# LEDDisplays-v00.net
KiCad netlist of a schematic drawn in EAGLE
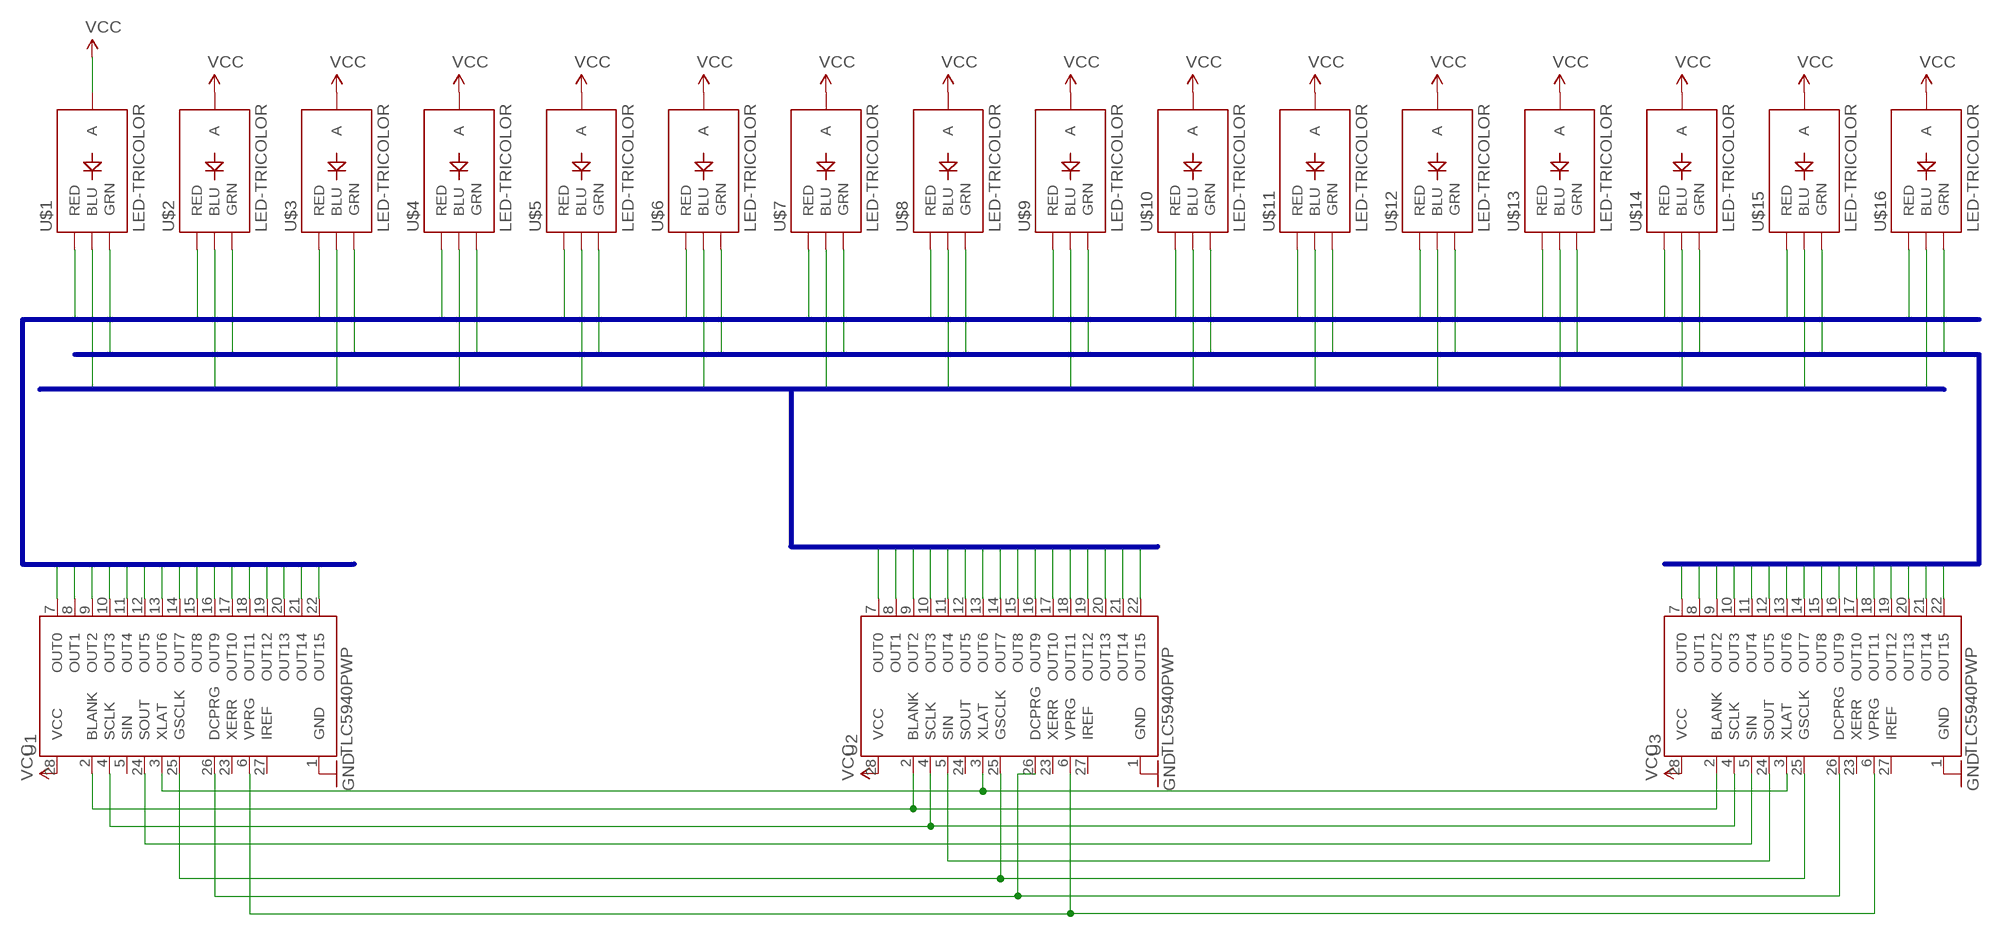
[diagram p0: schematic, sheet 1]

(export (version "E")
  (design (tool "Eeschema 10.0.6"))
  (components
    (comp (ref "U$1")
      (value "LED-TRICOLOR")
      (footprint "eagle-import:LED-TRICOLOR-SMD")
      (libsource (lib "eagle-import") (part "LED-TRICOLOR"))
    )
    (comp (ref "U$2")
      (value "LED-TRICOLOR")
      (footprint "eagle-import:LED-TRICOLOR-SMD")
      (libsource (lib "eagle-import") (part "LED-TRICOLOR"))
    )
    (comp (ref "U$3")
      (value "LED-TRICOLOR")
      (footprint "eagle-import:LED-TRICOLOR-SMD")
      (libsource (lib "eagle-import") (part "LED-TRICOLOR"))
    )
    (comp (ref "U$4")
      (value "LED-TRICOLOR")
      (footprint "eagle-import:LED-TRICOLOR-SMD")
      (libsource (lib "eagle-import") (part "LED-TRICOLOR"))
    )
    (comp (ref "U$5")
      (value "LED-TRICOLOR")
      (footprint "eagle-import:LED-TRICOLOR-SMD")
      (libsource (lib "eagle-import") (part "LED-TRICOLOR"))
    )
    (comp (ref "U$6")
      (value "LED-TRICOLOR")
      (footprint "eagle-import:LED-TRICOLOR-SMD")
      (libsource (lib "eagle-import") (part "LED-TRICOLOR"))
    )
    (comp (ref "U$7")
      (value "LED-TRICOLOR")
      (footprint "eagle-import:LED-TRICOLOR-SMD")
      (libsource (lib "eagle-import") (part "LED-TRICOLOR"))
    )
    (comp (ref "U$8")
      (value "LED-TRICOLOR")
      (footprint "eagle-import:LED-TRICOLOR-SMD")
      (libsource (lib "eagle-import") (part "LED-TRICOLOR"))
    )
    (comp (ref "U$9")
      (value "LED-TRICOLOR")
      (footprint "eagle-import:LED-TRICOLOR-SMD")
      (libsource (lib "eagle-import") (part "LED-TRICOLOR"))
    )
    (comp (ref "U$10")
      (value "LED-TRICOLOR")
      (footprint "eagle-import:LED-TRICOLOR-SMD")
      (libsource (lib "eagle-import") (part "LED-TRICOLOR"))
    )
    (comp (ref "U$11")
      (value "LED-TRICOLOR")
      (footprint "eagle-import:LED-TRICOLOR-SMD")
      (libsource (lib "eagle-import") (part "LED-TRICOLOR"))
    )
    (comp (ref "U$12")
      (value "LED-TRICOLOR")
      (footprint "eagle-import:LED-TRICOLOR-SMD")
      (libsource (lib "eagle-import") (part "LED-TRICOLOR"))
    )
    (comp (ref "U$13")
      (value "LED-TRICOLOR")
      (footprint "eagle-import:LED-TRICOLOR-SMD")
      (libsource (lib "eagle-import") (part "LED-TRICOLOR"))
    )
    (comp (ref "U$14")
      (value "LED-TRICOLOR")
      (footprint "eagle-import:LED-TRICOLOR-SMD")
      (libsource (lib "eagle-import") (part "LED-TRICOLOR"))
    )
    (comp (ref "U$15")
      (value "LED-TRICOLOR")
      (footprint "eagle-import:LED-TRICOLOR-SMD")
      (libsource (lib "eagle-import") (part "LED-TRICOLOR"))
    )
    (comp (ref "U$16")
      (value "LED-TRICOLOR")
      (footprint "eagle-import:LED-TRICOLOR-SMD")
      (libsource (lib "eagle-import") (part "LED-TRICOLOR"))
    )
    (comp (ref "U1")
      (value "TLC5940PWP")
      (footprint "eagle-import:TSSOP28-GROUNDPAD")
      (libsource (lib "eagle-import") (part "TLC5940PWP"))
    )
    (comp (ref "U2")
      (value "TLC5940PWP")
      (footprint "eagle-import:TSSOP28-GROUNDPAD")
      (libsource (lib "eagle-import") (part "TLC5940PWP"))
    )
    (comp (ref "U3")
      (value "TLC5940PWP")
      (footprint "eagle-import:TSSOP28-GROUNDPAD")
      (libsource (lib "eagle-import") (part "TLC5940PWP"))
    )
  )
  (nets
    (net (code "1") (name "/B1") (class "Default")
      (node (ref "U$1") (pin "B") (pinfunction "BLU_B") (pintype "bidirectional"))
      (node (ref "U2") (pin "7") (pinfunction "OUT0_7") (pintype "bidirectional"))
    )
    (net (code "2") (name "/B2") (class "Default")
      (node (ref "U$2") (pin "B") (pinfunction "BLU_B") (pintype "bidirectional"))
      (node (ref "U2") (pin "8") (pinfunction "OUT1_8") (pintype "bidirectional"))
    )
    (net (code "3") (name "/B3") (class "Default")
      (node (ref "U$3") (pin "B") (pinfunction "BLU_B") (pintype "bidirectional"))
      (node (ref "U2") (pin "9") (pinfunction "OUT2_9") (pintype "bidirectional"))
    )
    (net (code "4") (name "/B4") (class "Default")
      (node (ref "U$4") (pin "B") (pinfunction "BLU_B") (pintype "bidirectional"))
      (node (ref "U2") (pin "10") (pinfunction "OUT3_10") (pintype "bidirectional"))
    )
    (net (code "5") (name "/B5") (class "Default")
      (node (ref "U$5") (pin "B") (pinfunction "BLU_B") (pintype "bidirectional"))
      (node (ref "U2") (pin "11") (pinfunction "OUT4_11") (pintype "bidirectional"))
    )
    (net (code "6") (name "/B6") (class "Default")
      (node (ref "U$6") (pin "B") (pinfunction "BLU_B") (pintype "bidirectional"))
      (node (ref "U2") (pin "12") (pinfunction "OUT5_12") (pintype "bidirectional"))
    )
    (net (code "7") (name "/B7") (class "Default")
      (node (ref "U$7") (pin "B") (pinfunction "BLU_B") (pintype "bidirectional"))
      (node (ref "U2") (pin "13") (pinfunction "OUT6_13") (pintype "bidirectional"))
    )
    (net (code "8") (name "/B8") (class "Default")
      (node (ref "U$8") (pin "B") (pinfunction "BLU_B") (pintype "bidirectional"))
      (node (ref "U2") (pin "14") (pinfunction "OUT7_14") (pintype "bidirectional"))
    )
    (net (code "9") (name "/B9") (class "Default")
      (node (ref "U$9") (pin "B") (pinfunction "BLU_B") (pintype "bidirectional"))
      (node (ref "U2") (pin "15") (pinfunction "OUT8_15") (pintype "bidirectional"))
    )
    (net (code "10") (name "/B10") (class "Default")
      (node (ref "U$10") (pin "B") (pinfunction "BLU_B") (pintype "bidirectional"))
      (node (ref "U2") (pin "16") (pinfunction "OUT9_16") (pintype "bidirectional"))
    )
    (net (code "11") (name "/B11") (class "Default")
      (node (ref "U$11") (pin "B") (pinfunction "BLU_B") (pintype "bidirectional"))
      (node (ref "U2") (pin "17") (pinfunction "OUT10_17") (pintype "bidirectional"))
    )
    (net (code "12") (name "/B12") (class "Default")
      (node (ref "U$12") (pin "B") (pinfunction "BLU_B") (pintype "bidirectional"))
      (node (ref "U2") (pin "18") (pinfunction "OUT11_18") (pintype "bidirectional"))
    )
    (net (code "13") (name "/B13") (class "Default")
      (node (ref "U$13") (pin "B") (pinfunction "BLU_B") (pintype "bidirectional"))
      (node (ref "U2") (pin "19") (pinfunction "OUT12_19") (pintype "bidirectional"))
    )
    (net (code "14") (name "/B14") (class "Default")
      (node (ref "U$14") (pin "B") (pinfunction "BLU_B") (pintype "bidirectional"))
      (node (ref "U2") (pin "20") (pinfunction "OUT13_20") (pintype "bidirectional"))
    )
    (net (code "15") (name "/B15") (class "Default")
      (node (ref "U$15") (pin "B") (pinfunction "BLU_B") (pintype "bidirectional"))
      (node (ref "U2") (pin "21") (pinfunction "OUT14_21") (pintype "bidirectional"))
    )
    (net (code "16") (name "/B16") (class "Default")
      (node (ref "U$16") (pin "B") (pinfunction "BLU_B") (pintype "bidirectional"))
      (node (ref "U2") (pin "22") (pinfunction "OUT15_22") (pintype "bidirectional"))
    )
    (net (code "17") (name "/G1") (class "Default")
      (node (ref "U$1") (pin "G") (pinfunction "GRN_G") (pintype "bidirectional"))
      (node (ref "U3") (pin "7") (pinfunction "OUT0_7") (pintype "bidirectional"))
    )
    (net (code "18") (name "/G2") (class "Default")
      (node (ref "U$2") (pin "G") (pinfunction "GRN_G") (pintype "bidirectional"))
      (node (ref "U3") (pin "8") (pinfunction "OUT1_8") (pintype "bidirectional"))
    )
    (net (code "19") (name "/G3") (class "Default")
      (node (ref "U$3") (pin "G") (pinfunction "GRN_G") (pintype "bidirectional"))
      (node (ref "U3") (pin "9") (pinfunction "OUT2_9") (pintype "bidirectional"))
    )
    (net (code "20") (name "/G4") (class "Default")
      (node (ref "U$4") (pin "G") (pinfunction "GRN_G") (pintype "bidirectional"))
      (node (ref "U3") (pin "10") (pinfunction "OUT3_10") (pintype "bidirectional"))
    )
    (net (code "21") (name "/G5") (class "Default")
      (node (ref "U$5") (pin "G") (pinfunction "GRN_G") (pintype "bidirectional"))
      (node (ref "U3") (pin "11") (pinfunction "OUT4_11") (pintype "bidirectional"))
    )
    (net (code "22") (name "/G6") (class "Default")
      (node (ref "U$6") (pin "G") (pinfunction "GRN_G") (pintype "bidirectional"))
      (node (ref "U3") (pin "12") (pinfunction "OUT5_12") (pintype "bidirectional"))
    )
    (net (code "23") (name "/G7") (class "Default")
      (node (ref "U$7") (pin "G") (pinfunction "GRN_G") (pintype "bidirectional"))
      (node (ref "U3") (pin "13") (pinfunction "OUT6_13") (pintype "bidirectional"))
    )
    (net (code "24") (name "/G8") (class "Default")
      (node (ref "U$8") (pin "G") (pinfunction "GRN_G") (pintype "bidirectional"))
      (node (ref "U3") (pin "14") (pinfunction "OUT7_14") (pintype "bidirectional"))
    )
    (net (code "25") (name "/G9") (class "Default")
      (node (ref "U$9") (pin "G") (pinfunction "GRN_G") (pintype "bidirectional"))
      (node (ref "U3") (pin "15") (pinfunction "OUT8_15") (pintype "bidirectional"))
    )
    (net (code "26") (name "/G10") (class "Default")
      (node (ref "U$10") (pin "G") (pinfunction "GRN_G") (pintype "bidirectional"))
      (node (ref "U3") (pin "16") (pinfunction "OUT9_16") (pintype "bidirectional"))
    )
    (net (code "27") (name "/G11") (class "Default")
      (node (ref "U$11") (pin "G") (pinfunction "GRN_G") (pintype "bidirectional"))
      (node (ref "U3") (pin "17") (pinfunction "OUT10_17") (pintype "bidirectional"))
    )
    (net (code "28") (name "/G12") (class "Default")
      (node (ref "U$12") (pin "G") (pinfunction "GRN_G") (pintype "bidirectional"))
      (node (ref "U3") (pin "18") (pinfunction "OUT11_18") (pintype "bidirectional"))
    )
    (net (code "29") (name "/G13") (class "Default")
      (node (ref "U$13") (pin "G") (pinfunction "GRN_G") (pintype "bidirectional"))
      (node (ref "U3") (pin "19") (pinfunction "OUT12_19") (pintype "bidirectional"))
    )
    (net (code "30") (name "/G14") (class "Default")
      (node (ref "U$14") (pin "G") (pinfunction "GRN_G") (pintype "bidirectional"))
      (node (ref "U3") (pin "20") (pinfunction "OUT13_20") (pintype "bidirectional"))
    )
    (net (code "31") (name "/G15") (class "Default")
      (node (ref "U$15") (pin "G") (pinfunction "GRN_G") (pintype "bidirectional"))
      (node (ref "U3") (pin "21") (pinfunction "OUT14_21") (pintype "bidirectional"))
    )
    (net (code "32") (name "/G16") (class "Default")
      (node (ref "U$16") (pin "G") (pinfunction "GRN_G") (pintype "bidirectional"))
      (node (ref "U3") (pin "22") (pinfunction "OUT15_22") (pintype "bidirectional"))
    )
    (net (code "33") (name "/R1") (class "Default")
      (node (ref "U$1") (pin "R") (pinfunction "RED_R") (pintype "bidirectional"))
      (node (ref "U1") (pin "7") (pinfunction "OUT0_7") (pintype "bidirectional"))
    )
    (net (code "34") (name "/R2") (class "Default")
      (node (ref "U$2") (pin "R") (pinfunction "RED_R") (pintype "bidirectional"))
      (node (ref "U1") (pin "8") (pinfunction "OUT1_8") (pintype "bidirectional"))
    )
    (net (code "35") (name "/R3") (class "Default")
      (node (ref "U$3") (pin "R") (pinfunction "RED_R") (pintype "bidirectional"))
      (node (ref "U1") (pin "9") (pinfunction "OUT2_9") (pintype "bidirectional"))
    )
    (net (code "36") (name "/R4") (class "Default")
      (node (ref "U$4") (pin "R") (pinfunction "RED_R") (pintype "bidirectional"))
      (node (ref "U1") (pin "10") (pinfunction "OUT3_10") (pintype "bidirectional"))
    )
    (net (code "37") (name "/R5") (class "Default")
      (node (ref "U$5") (pin "R") (pinfunction "RED_R") (pintype "bidirectional"))
      (node (ref "U1") (pin "11") (pinfunction "OUT4_11") (pintype "bidirectional"))
    )
    (net (code "38") (name "/R6") (class "Default")
      (node (ref "U$6") (pin "R") (pinfunction "RED_R") (pintype "bidirectional"))
      (node (ref "U1") (pin "12") (pinfunction "OUT5_12") (pintype "bidirectional"))
    )
    (net (code "39") (name "/R7") (class "Default")
      (node (ref "U$7") (pin "R") (pinfunction "RED_R") (pintype "bidirectional"))
      (node (ref "U1") (pin "13") (pinfunction "OUT6_13") (pintype "bidirectional"))
    )
    (net (code "40") (name "/R8") (class "Default")
      (node (ref "U$8") (pin "R") (pinfunction "RED_R") (pintype "bidirectional"))
      (node (ref "U1") (pin "14") (pinfunction "OUT7_14") (pintype "bidirectional"))
    )
    (net (code "41") (name "/R9") (class "Default")
      (node (ref "U$9") (pin "R") (pinfunction "RED_R") (pintype "bidirectional"))
      (node (ref "U1") (pin "15") (pinfunction "OUT8_15") (pintype "bidirectional"))
    )
    (net (code "42") (name "/R10") (class "Default")
      (node (ref "U$10") (pin "R") (pinfunction "RED_R") (pintype "bidirectional"))
      (node (ref "U1") (pin "16") (pinfunction "OUT9_16") (pintype "bidirectional"))
    )
    (net (code "43") (name "/R11") (class "Default")
      (node (ref "U$11") (pin "R") (pinfunction "RED_R") (pintype "bidirectional"))
      (node (ref "U1") (pin "17") (pinfunction "OUT10_17") (pintype "bidirectional"))
    )
    (net (code "44") (name "/R12") (class "Default")
      (node (ref "U$12") (pin "R") (pinfunction "RED_R") (pintype "bidirectional"))
      (node (ref "U1") (pin "18") (pinfunction "OUT11_18") (pintype "bidirectional"))
    )
    (net (code "45") (name "/R13") (class "Default")
      (node (ref "U$13") (pin "R") (pinfunction "RED_R") (pintype "bidirectional"))
      (node (ref "U1") (pin "19") (pinfunction "OUT12_19") (pintype "bidirectional"))
    )
    (net (code "46") (name "/R14") (class "Default")
      (node (ref "U$14") (pin "R") (pinfunction "RED_R") (pintype "bidirectional"))
      (node (ref "U1") (pin "20") (pinfunction "OUT13_20") (pintype "bidirectional"))
    )
    (net (code "47") (name "/R15") (class "Default")
      (node (ref "U$15") (pin "R") (pinfunction "RED_R") (pintype "bidirectional"))
      (node (ref "U1") (pin "21") (pinfunction "OUT14_21") (pintype "bidirectional"))
    )
    (net (code "48") (name "/R16") (class "Default")
      (node (ref "U$16") (pin "R") (pinfunction "RED_R") (pintype "bidirectional"))
      (node (ref "U1") (pin "22") (pinfunction "OUT15_22") (pintype "bidirectional"))
    )
    (net (code "49") (name "GND") (class "Default")
      (node (ref "U1") (pin "1") (pinfunction "GND_1") (pintype "bidirectional"))
      (node (ref "U2") (pin "1") (pinfunction "GND_1") (pintype "bidirectional"))
      (node (ref "U3") (pin "1") (pinfunction "GND_1") (pintype "bidirectional"))
    )
    (net (code "50") (name "Net-(U1-BLANK)") (class "Default")
      (node (ref "U1") (pin "2") (pinfunction "BLANK_2") (pintype "bidirectional"))
      (node (ref "U2") (pin "2") (pinfunction "BLANK_2") (pintype "bidirectional"))
      (node (ref "U3") (pin "2") (pinfunction "BLANK_2") (pintype "bidirectional"))
    )
    (net (code "51") (name "Net-(U1-DCPRG)") (class "Default")
      (node (ref "U1") (pin "26") (pinfunction "DCPRG_26") (pintype "bidirectional"))
      (node (ref "U2") (pin "26") (pinfunction "DCPRG_26") (pintype "bidirectional"))
      (node (ref "U3") (pin "26") (pinfunction "DCPRG_26") (pintype "bidirectional"))
    )
    (net (code "52") (name "Net-(U1-GSCLK)") (class "Default")
      (node (ref "U1") (pin "25") (pinfunction "GSCLK_25") (pintype "bidirectional"))
      (node (ref "U2") (pin "25") (pinfunction "GSCLK_25") (pintype "bidirectional"))
      (node (ref "U3") (pin "25") (pinfunction "GSCLK_25") (pintype "bidirectional"))
    )
    (net (code "53") (name "Net-(U1-SCLK)") (class "Default")
      (node (ref "U1") (pin "4") (pinfunction "SCLK_4") (pintype "bidirectional"))
      (node (ref "U2") (pin "4") (pinfunction "SCLK_4") (pintype "bidirectional"))
      (node (ref "U3") (pin "4") (pinfunction "SCLK_4") (pintype "bidirectional"))
    )
    (net (code "54") (name "Net-(U1-SOUT)") (class "Default")
      (node (ref "U1") (pin "24") (pinfunction "SOUT_24") (pintype "bidirectional"))
      (node (ref "U3") (pin "5") (pinfunction "SIN_5") (pintype "bidirectional"))
    )
    (net (code "55") (name "Net-(U1-VPRG)") (class "Default")
      (node (ref "U1") (pin "6") (pinfunction "VPRG_6") (pintype "bidirectional"))
      (node (ref "U2") (pin "6") (pinfunction "VPRG_6") (pintype "bidirectional"))
      (node (ref "U3") (pin "6") (pinfunction "VPRG_6") (pintype "bidirectional"))
    )
    (net (code "56") (name "Net-(U1-XLAT)") (class "Default")
      (node (ref "U1") (pin "3") (pinfunction "XLAT_3") (pintype "bidirectional"))
      (node (ref "U2") (pin "3") (pinfunction "XLAT_3") (pintype "bidirectional"))
      (node (ref "U3") (pin "3") (pinfunction "XLAT_3") (pintype "bidirectional"))
    )
    (net (code "57") (name "Net-(U2-SIN)") (class "Default")
      (node (ref "U2") (pin "5") (pinfunction "SIN_5") (pintype "bidirectional"))
      (node (ref "U3") (pin "24") (pinfunction "SOUT_24") (pintype "bidirectional"))
    )
    (net (code "58") (name "VCC") (class "Default")
      (node (ref "U$1") (pin "A") (pinfunction "A_A") (pintype "bidirectional"))
      (node (ref "U$10") (pin "A") (pinfunction "A_A") (pintype "bidirectional"))
      (node (ref "U$11") (pin "A") (pinfunction "A_A") (pintype "bidirectional"))
      (node (ref "U$12") (pin "A") (pinfunction "A_A") (pintype "bidirectional"))
      (node (ref "U$13") (pin "A") (pinfunction "A_A") (pintype "bidirectional"))
      (node (ref "U$14") (pin "A") (pinfunction "A_A") (pintype "bidirectional"))
      (node (ref "U$15") (pin "A") (pinfunction "A_A") (pintype "bidirectional"))
      (node (ref "U$16") (pin "A") (pinfunction "A_A") (pintype "bidirectional"))
      (node (ref "U$2") (pin "A") (pinfunction "A_A") (pintype "bidirectional"))
      (node (ref "U$3") (pin "A") (pinfunction "A_A") (pintype "bidirectional"))
      (node (ref "U$4") (pin "A") (pinfunction "A_A") (pintype "bidirectional"))
      (node (ref "U$5") (pin "A") (pinfunction "A_A") (pintype "bidirectional"))
      (node (ref "U$6") (pin "A") (pinfunction "A_A") (pintype "bidirectional"))
      (node (ref "U$7") (pin "A") (pinfunction "A_A") (pintype "bidirectional"))
      (node (ref "U$8") (pin "A") (pinfunction "A_A") (pintype "bidirectional"))
      (node (ref "U$9") (pin "A") (pinfunction "A_A") (pintype "bidirectional"))
      (node (ref "U1") (pin "28") (pinfunction "VCC_28") (pintype "bidirectional"))
      (node (ref "U2") (pin "28") (pinfunction "VCC_28") (pintype "bidirectional"))
      (node (ref "U3") (pin "28") (pinfunction "VCC_28") (pintype "bidirectional"))
    )
    (net (code "59") (name "unconnected-(U1-IREF-Pad27)") (class "Default")
      (node (ref "U1") (pin "27") (pinfunction "IREF_27") (pintype "bidirectional"))
    )
    (net (code "60") (name "unconnected-(U1-SIN-Pad5)") (class "Default")
      (node (ref "U1") (pin "5") (pinfunction "SIN_5") (pintype "bidirectional"))
    )
    (net (code "61") (name "unconnected-(U1-XERR-Pad23)") (class "Default")
      (node (ref "U1") (pin "23") (pinfunction "XERR_23") (pintype "bidirectional"))
    )
    (net (code "62") (name "unconnected-(U2-IREF-Pad27)") (class "Default")
      (node (ref "U2") (pin "27") (pinfunction "IREF_27") (pintype "bidirectional"))
    )
    (net (code "63") (name "unconnected-(U2-SOUT-Pad24)") (class "Default")
      (node (ref "U2") (pin "24") (pinfunction "SOUT_24") (pintype "bidirectional"))
    )
    (net (code "64") (name "unconnected-(U2-XERR-Pad23)") (class "Default")
      (node (ref "U2") (pin "23") (pinfunction "XERR_23") (pintype "bidirectional"))
    )
    (net (code "65") (name "unconnected-(U3-IREF-Pad27)") (class "Default")
      (node (ref "U3") (pin "27") (pinfunction "IREF_27") (pintype "bidirectional"))
    )
    (net (code "66") (name "unconnected-(U3-XERR-Pad23)") (class "Default")
      (node (ref "U3") (pin "23") (pinfunction "XERR_23") (pintype "bidirectional"))
    )
  )
)
